# schematics.net
KiCad netlist of a schematic drawn in Altium Designer
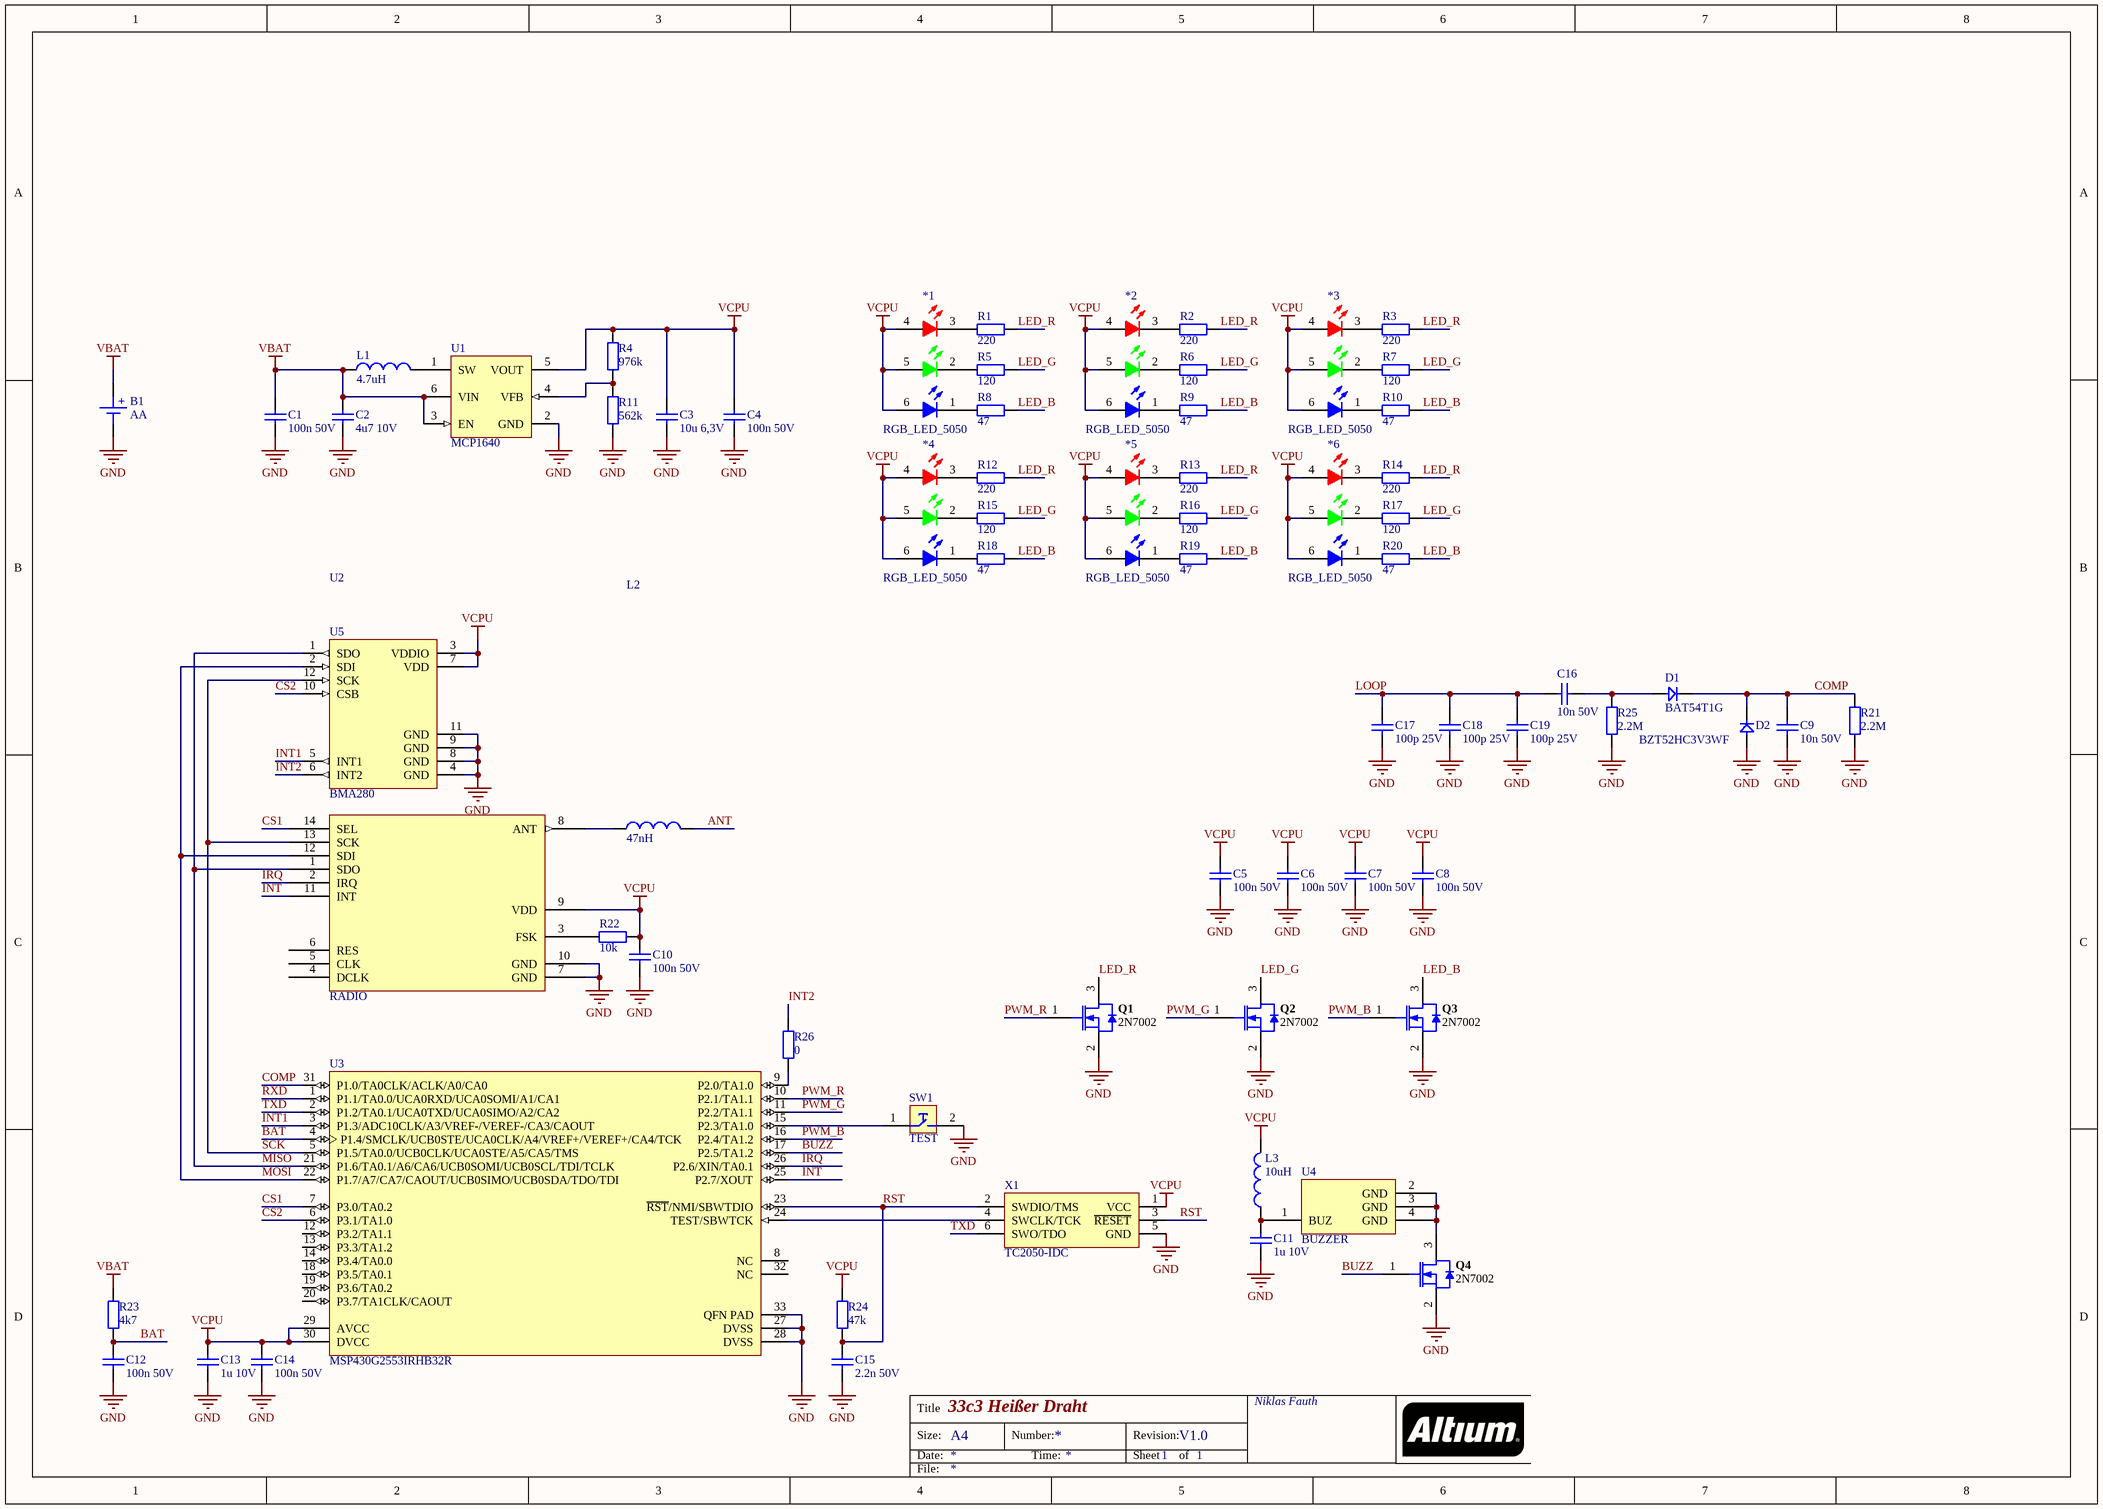
[diagram p0: schematics.SchDoc]

(export (version "E")
  (design (tool "Eeschema 10.0.6"))
  (components
    (comp (ref "*1")
      (value "RGB_LED_5050")
      (footprint "plcc6")
      (libsource (lib "advanced") (part "RGB_LED_5050"))
    )
    (comp (ref "*2")
      (value "RGB_LED_5050")
      (footprint "plcc6")
      (libsource (lib "advanced") (part "RGB_LED_5050"))
    )
    (comp (ref "*3")
      (value "RGB_LED_5050")
      (footprint "plcc6")
      (libsource (lib "advanced") (part "RGB_LED_5050"))
    )
    (comp (ref "*4")
      (value "RGB_LED_5050")
      (footprint "plcc6")
      (libsource (lib "advanced") (part "RGB_LED_5050"))
    )
    (comp (ref "*5")
      (value "RGB_LED_5050")
      (footprint "plcc6")
      (libsource (lib "advanced") (part "RGB_LED_5050"))
    )
    (comp (ref "*6")
      (value "RGB_LED_5050")
      (footprint "plcc6")
      (libsource (lib "advanced") (part "RGB_LED_5050"))
    )
    (comp (ref "B1")
      (value "AA")
      (footprint "AA-HOLDER")
      (description "Batt Holder AA")
      (libsource (lib "advanced") (part "AA-Batt-Holder"))
    )
    (comp (ref "C1")
      (value "100n 50V")
      (footprint "C-0603-M")
      (description "Capacitor 100n 50V")
      (libsource (lib "Passives") (part "C-0603-100n-50V"))
    )
    (comp (ref "C2")
      (value "4u7 10V")
      (footprint "C-0603-H")
      (description "Capacitor 4.7uF 10V")
      (libsource (lib "Passives") (part "C-0603-4u7-10V"))
    )
    (comp (ref "C3")
      (value "10u 6,3V")
      (footprint "C-0603-H")
      (description "Capacitor 10uF 6,3V")
      (libsource (lib "Passives") (part "C-0603-10u-6,3V"))
    )
    (comp (ref "C4")
      (value "100n 50V")
      (footprint "C-0603-M")
      (description "Capacitor 100n 50V")
      (libsource (lib "Passives") (part "C-0603-100n-50V"))
    )
    (comp (ref "C5")
      (value "100n 50V")
      (footprint "C-0603-M")
      (description "Capacitor 100n 50V")
      (libsource (lib "Passives") (part "C-0603-100n-50V"))
    )
    (comp (ref "C6")
      (value "100n 50V")
      (footprint "C-0603-M")
      (description "Capacitor 100n 50V")
      (libsource (lib "Passives") (part "C-0603-100n-50V"))
    )
    (comp (ref "C7")
      (value "100n 50V")
      (footprint "C-0603-M")
      (description "Capacitor 100n 50V")
      (libsource (lib "Passives") (part "C-0603-100n-50V"))
    )
    (comp (ref "C8")
      (value "100n 50V")
      (footprint "C-0603-M")
      (description "Capacitor 100n 50V")
      (libsource (lib "Passives") (part "C-0603-100n-50V"))
    )
    (comp (ref "C9")
      (value "10n 50V")
      (footprint "C-0603-H")
      (description "Capacitor 10nF 50V")
      (libsource (lib "Passives") (part "C-0603-10n-50V"))
    )
    (comp (ref "C10")
      (value "100n 50V")
      (footprint "C-0603-M")
      (description "Capacitor 100n 50V")
      (libsource (lib "Passives") (part "C-0603-100n-50V"))
    )
    (comp (ref "C11")
      (value "1u 10V")
      (footprint "C-0603-H")
      (description "Capacitor 1uF 10V")
      (libsource (lib "Passives") (part "C-0603-1u-10V"))
    )
    (comp (ref "C12")
      (value "100n 50V")
      (footprint "C-0603-M")
      (description "Capacitor 100n 50V")
      (libsource (lib "Passives") (part "C-0603-100n-50V"))
    )
    (comp (ref "C13")
      (value "1u 10V")
      (footprint "C-0603-H")
      (description "Capacitor 1uF 10V")
      (libsource (lib "Passives") (part "C-0603-1u-10V"))
    )
    (comp (ref "C14")
      (value "100n 50V")
      (footprint "C-0603-M")
      (description "Capacitor 100n 50V")
      (libsource (lib "Passives") (part "C-0603-100n-50V"))
    )
    (comp (ref "C15")
      (value "2.2n 50V")
      (footprint "C-0603-H")
      (description "Capacitor 2.2n 50V")
      (libsource (lib "Passives") (part "C-0603-2n2-50V"))
    )
    (comp (ref "C16")
      (value "10n 50V")
      (footprint "C-0603-H")
      (description "Capacitor 10nF 50V")
      (libsource (lib "Passives") (part "C-0603-10n-50V"))
    )
    (comp (ref "C17")
      (value "100p 25V")
      (footprint "C-0603-M")
      (description "Capacitor 100pF 25V")
      (libsource (lib "Passives") (part "C-0603-100p-25V"))
    )
    (comp (ref "C18")
      (value "100p 25V")
      (footprint "C-0603-M")
      (description "Capacitor 100pF 25V")
      (libsource (lib "Passives") (part "C-0603-100p-25V"))
    )
    (comp (ref "C19")
      (value "100p 25V")
      (footprint "C-0603-M")
      (description "Capacitor 100pF 25V")
      (libsource (lib "Passives") (part "C-0603-100p-25V"))
    )
    (comp (ref "D1") (value "BAT54T1G") (footprint "SOD123") (libsource (lib "advanced") (part "BAT54T1G")))
    (comp (ref "D2")
      (value "BZT52HC3V3WF")
      (footprint "SOD123")
      (description "BAT54T1G")
      (libsource (lib "advanced") (part "BAT54T1G"))
    )
    (comp (ref "L1")
      (value "4.7uH")
      (footprint "SRN4012")
      (description "SRN4012TA-4R7M")
      (libsource (lib "advanced") (part "L-SRN4012TA-4R7M"))
    )
    (comp (ref "L2") (value "47nH") (footprint "C-0603-M") (libsource (lib "advanced") (part "L-0603-47nH")))
    (comp (ref "L3")
      (value "10uH")
      (footprint "R-0805")
      (description "L 0805 10uH")
      (libsource (lib "advanced") (part "L-0805-10uH"))
    )
    (comp (ref "Q1")
      (value "2N7002")
      (footprint "INF-PG-SOT23_M")
      (fields (field (name "MANUFACTURER") "Infineon"))
      (libsource (lib "Altium Content Vault") (part "INF-NDMOS-GSD-3"))
    )
    (comp (ref "Q2")
      (value "2N7002")
      (footprint "INF-PG-SOT23_M")
      (fields (field (name "MANUFACTURER") "Infineon"))
      (libsource (lib "Altium Content Vault") (part "INF-NDMOS-GSD-3"))
    )
    (comp (ref "Q3")
      (value "2N7002")
      (footprint "INF-PG-SOT23_M")
      (fields (field (name "MANUFACTURER") "Infineon"))
      (libsource (lib "Altium Content Vault") (part "INF-NDMOS-GSD-3"))
    )
    (comp (ref "Q4")
      (value "2N7002")
      (footprint "INF-PG-SOT23_M")
      (fields (field (name "MANUFACTURER") "Infineon"))
      (libsource (lib "Altium Content Vault") (part "INF-NDMOS-GSD-3"))
    )
    (comp (ref "R1")
      (value "220")
      (footprint "R-0603-M")
      (description "Resistor 220")
      (libsource (lib "Passives") (part "R-0603-220"))
    )
    (comp (ref "R2")
      (value "220")
      (footprint "R-0603-M")
      (description "Resistor 220")
      (libsource (lib "Passives") (part "R-0603-220"))
    )
    (comp (ref "R3")
      (value "220")
      (footprint "R-0603-M")
      (description "Resistor 220")
      (libsource (lib "Passives") (part "R-0603-220"))
    )
    (comp (ref "R4")
      (value "976k")
      (footprint "R-0603-M")
      (description "Resistor 976k")
      (libsource (lib "Passives") (part "R-0603-976k"))
    )
    (comp (ref "R5")
      (value "120")
      (footprint "R-0603-M")
      (description "Resistor 120")
      (libsource (lib "Passives") (part "R-0603-120"))
    )
    (comp (ref "R6")
      (value "120")
      (footprint "R-0603-M")
      (description "Resistor 120")
      (libsource (lib "Passives") (part "R-0603-120"))
    )
    (comp (ref "R7")
      (value "120")
      (footprint "R-0603-M")
      (description "Resistor 120")
      (libsource (lib "Passives") (part "R-0603-120"))
    )
    (comp (ref "R8")
      (value "47")
      (footprint "R-0603-M")
      (description "Resistor 47")
      (libsource (lib "Passives") (part "R-0603-47"))
    )
    (comp (ref "R9")
      (value "47")
      (footprint "R-0603-M")
      (description "Resistor 47")
      (libsource (lib "Passives") (part "R-0603-47"))
    )
    (comp (ref "R10")
      (value "47")
      (footprint "R-0603-M")
      (description "Resistor 47")
      (libsource (lib "Passives") (part "R-0603-47"))
    )
    (comp (ref "R11")
      (value "562k")
      (footprint "R-0603-M")
      (description "Resistor 562k")
      (libsource (lib "Passives") (part "R-0603-562k"))
    )
    (comp (ref "R12")
      (value "220")
      (footprint "R-0603-M")
      (description "Resistor 220")
      (libsource (lib "Passives") (part "R-0603-220"))
    )
    (comp (ref "R13")
      (value "220")
      (footprint "R-0603-M")
      (description "Resistor 220")
      (libsource (lib "Passives") (part "R-0603-220"))
    )
    (comp (ref "R14")
      (value "220")
      (footprint "R-0603-M")
      (description "Resistor 220")
      (libsource (lib "Passives") (part "R-0603-220"))
    )
    (comp (ref "R15")
      (value "120")
      (footprint "R-0603-M")
      (description "Resistor 120")
      (libsource (lib "Passives") (part "R-0603-120"))
    )
    (comp (ref "R16")
      (value "120")
      (footprint "R-0603-M")
      (description "Resistor 120")
      (libsource (lib "Passives") (part "R-0603-120"))
    )
    (comp (ref "R17")
      (value "120")
      (footprint "R-0603-M")
      (description "Resistor 120")
      (libsource (lib "Passives") (part "R-0603-120"))
    )
    (comp (ref "R18")
      (value "47")
      (footprint "R-0603-M")
      (description "Resistor 47")
      (libsource (lib "Passives") (part "R-0603-47"))
    )
    (comp (ref "R19")
      (value "47")
      (footprint "R-0603-M")
      (description "Resistor 47")
      (libsource (lib "Passives") (part "R-0603-47"))
    )
    (comp (ref "R20")
      (value "47")
      (footprint "R-0603-M")
      (description "Resistor 47")
      (libsource (lib "Passives") (part "R-0603-47"))
    )
    (comp (ref "R21")
      (value "2.2M")
      (footprint "R-0603-H")
      (description "Resistor 2.2M")
      (libsource (lib "Passives") (part "R-0603-2M2"))
    )
    (comp (ref "R22")
      (value "10k")
      (footprint "R-0603-M")
      (description "Resistor 10k")
      (libsource (lib "Passives") (part "R-0603-10k"))
    )
    (comp (ref "R23")
      (value "4k7")
      (footprint "R-0603-H")
      (description "Resistor 4k7")
      (libsource (lib "Passives") (part "R-0603-4k7"))
    )
    (comp (ref "R24")
      (value "47k")
      (footprint "R-0603-H")
      (description "Resistor 4k7")
      (libsource (lib "Passives") (part "R-0603-47k"))
    )
    (comp (ref "R25")
      (value "2.2M")
      (footprint "R-0603-H")
      (description "Resistor 2.2M")
      (libsource (lib "Passives") (part "R-0603-2M2"))
    )
    (comp (ref "R26")
      (value "0")
      (footprint "R-0603-M")
      (description "Resistor 0")
      (libsource (lib "Passives") (part "R-0603-0"))
    )
    (comp (ref "SW1")
      (value "TEST")
      (footprint "switch-mini-ALPS")
      (description "SKQYAAE010")
      (libsource (lib "advanced") (part "Switch-mini-ALPS"))
    )
    (comp (ref "U1")
      (value "MCP1640")
      (footprint "SOT23-6")
      (description "aaa to 3.3V")
      (libsource (lib "advanced") (part "MCP1640"))
    )
    (comp (ref "U2")
      (value "RADIO")
      (footprint "RFM12")
      (description "Sub 1GHz Radio Module")
      (libsource (lib "advanced") (part "RFM12"))
    )
    (comp (ref "U3")
      (value "MSP430G2553IRHB32R")
      (footprint "RHB0032E_V")
      (fields (field (name "MANUFACTURER") "Texas Instruments"))
      (libsource (lib "Altium Content Vault") (part "TI-MSP430G2X53-RHB32"))
    )
    (comp (ref "U4") (value "BUZZER") (footprint "PIEZO") (libsource (lib "advanced") (part "PIEZO-1411A03")))
    (comp (ref "U5")
      (value "BMA280")
      (footprint "LGA12C50P4X4_203X203X80")
      (libsource (lib "advanced") (part "BMA280"))
    )
    (comp (ref "X1")
      (value "TC2050-IDC")
      (footprint "TC2030-IDC-NL")
      (description "TC2050-IDC SWD")
      (libsource (lib "advanced") (part "TAG-Connect-SWD"))
    )
  )
  (nets
    (net (code "1") (name "/ANT") (class "Default")
      (node (ref "L2") (pin "2") (pinfunction "2_2") (pintype "passive"))
    )
    (net (code "2") (name "/BAT") (class "Default")
      (node (ref "C12") (pin "2") (pinfunction "2_2") (pintype "passive"))
      (node (ref "R23") (pin "1") (pinfunction "1_1") (pintype "passive"))
      (node (ref "U3") (pin "4") (pinfunction "P1.4/SMCLK/UCB0STE/UCA0CLK/A4/VREF+/VEREF+/CA4/TCK_4") (pintype "bidirectional"))
    )
    (net (code "3") (name "/BUZZ") (class "Default")
      (node (ref "Q4") (pin "1") (pinfunction "GATE_1") (pintype "passive"))
      (node (ref "U3") (pin "17") (pinfunction "P2.5/TA1.2_17") (pintype "bidirectional"))
    )
    (net (code "4") (name "/COMP") (class "Default")
      (node (ref "C9") (pin "2") (pinfunction "2_2") (pintype "passive"))
      (node (ref "D1") (pin "2") (pinfunction "kt_2") (pintype "passive"))
      (node (ref "D2") (pin "2") (pinfunction "kt_2") (pintype "passive"))
      (node (ref "R21") (pin "2") (pinfunction "2_2") (pintype "passive"))
      (node (ref "U3") (pin "31") (pinfunction "P1.0/TA0CLK/ACLK/A0/CA0_31") (pintype "bidirectional"))
    )
    (net (code "5") (name "/CS1") (class "Default")
      (node (ref "U2") (pin "14") (pinfunction "SEL_14") (pintype "passive"))
      (node (ref "U3") (pin "7") (pinfunction "P3.0/TA0.2_7") (pintype "bidirectional"))
    )
    (net (code "6") (name "/CS2") (class "Default")
      (node (ref "U3") (pin "6") (pinfunction "P3.1/TA1.0_6") (pintype "bidirectional"))
      (node (ref "U5") (pin "10") (pinfunction "CSB_10") (pintype "input"))
    )
    (net (code "7") (name "/INT") (class "Default")
      (node (ref "U2") (pin "11") (pinfunction "INT_11") (pintype "passive"))
      (node (ref "U3") (pin "25") (pinfunction "P2.7/XOUT_25") (pintype "bidirectional"))
    )
    (net (code "8") (name "/INT1") (class "Default")
      (node (ref "U3") (pin "3") (pinfunction "P1.3/ADC10CLK/A3/VREF-/VEREF-/CA3/CAOUT_3") (pintype "bidirectional"))
      (node (ref "U5") (pin "5") (pinfunction "INT1_5") (pintype "output"))
    )
    (net (code "9") (name "/INT2") (class "Default")
      (node (ref "R26") (pin "2") (pinfunction "2_2") (pintype "passive"))
      (node (ref "U5") (pin "6") (pinfunction "INT2_6") (pintype "output"))
    )
    (net (code "10") (name "/IRQ") (class "Default")
      (node (ref "U2") (pin "2") (pinfunction "IRQ_2") (pintype "passive"))
      (node (ref "U3") (pin "26") (pinfunction "P2.6/XIN/TA0.1_26") (pintype "bidirectional"))
    )
    (net (code "11") (name "/LED_B") (class "Default")
      (node (ref "Q3") (pin "3") (pinfunction "DRAIN_3") (pintype "passive"))
      (node (ref "R10") (pin "2") (pinfunction "2_2") (pintype "passive"))
      (node (ref "R18") (pin "2") (pinfunction "2_2") (pintype "passive"))
      (node (ref "R19") (pin "2") (pinfunction "2_2") (pintype "passive"))
      (node (ref "R20") (pin "2") (pinfunction "2_2") (pintype "passive"))
      (node (ref "R8") (pin "2") (pinfunction "2_2") (pintype "passive"))
      (node (ref "R9") (pin "2") (pinfunction "2_2") (pintype "passive"))
    )
    (net (code "12") (name "/LED_G") (class "Default")
      (node (ref "Q2") (pin "3") (pinfunction "DRAIN_3") (pintype "passive"))
      (node (ref "R15") (pin "2") (pinfunction "2_2") (pintype "passive"))
      (node (ref "R16") (pin "2") (pinfunction "2_2") (pintype "passive"))
      (node (ref "R17") (pin "2") (pinfunction "2_2") (pintype "passive"))
      (node (ref "R5") (pin "2") (pinfunction "2_2") (pintype "passive"))
      (node (ref "R6") (pin "2") (pinfunction "2_2") (pintype "passive"))
      (node (ref "R7") (pin "2") (pinfunction "2_2") (pintype "passive"))
    )
    (net (code "13") (name "/LED_R") (class "Default")
      (node (ref "Q1") (pin "3") (pinfunction "DRAIN_3") (pintype "passive"))
      (node (ref "R1") (pin "2") (pinfunction "2_2") (pintype "passive"))
      (node (ref "R12") (pin "2") (pinfunction "2_2") (pintype "passive"))
      (node (ref "R13") (pin "2") (pinfunction "2_2") (pintype "passive"))
      (node (ref "R14") (pin "2") (pinfunction "2_2") (pintype "passive"))
      (node (ref "R2") (pin "2") (pinfunction "2_2") (pintype "passive"))
      (node (ref "R3") (pin "2") (pinfunction "2_2") (pintype "passive"))
    )
    (net (code "14") (name "/LOOP") (class "Default")
      (node (ref "C16") (pin "1") (pinfunction "1_1") (pintype "passive"))
      (node (ref "C17") (pin "2") (pinfunction "2_2") (pintype "passive"))
      (node (ref "C18") (pin "2") (pinfunction "2_2") (pintype "passive"))
      (node (ref "C19") (pin "2") (pinfunction "2_2") (pintype "passive"))
    )
    (net (code "15") (name "/MISO") (class "Default")
      (node (ref "U2") (pin "1") (pinfunction "SDO_1") (pintype "passive"))
      (node (ref "U3") (pin "21") (pinfunction "P1.6/TA0.1/A6/CA6/UCB0SOMI/UCB0SCL/TDI/TCLK_21") (pintype "bidirectional"))
      (node (ref "U5") (pin "1") (pinfunction "SDO_1") (pintype "output"))
    )
    (net (code "16") (name "/MOSI") (class "Default")
      (node (ref "U2") (pin "12") (pinfunction "SDI_12") (pintype "passive"))
      (node (ref "U3") (pin "22") (pinfunction "P1.7/A7/CA7/CAOUT/UCB0SIMO/UCB0SDA/TDO/TDI_22") (pintype "bidirectional"))
      (node (ref "U5") (pin "2") (pinfunction "SDI_2") (pintype "input"))
    )
    (net (code "17") (name "/PWM_B") (class "Default")
      (node (ref "Q3") (pin "1") (pinfunction "GATE_1") (pintype "passive"))
      (node (ref "U3") (pin "16") (pinfunction "P2.4/TA1.2_16") (pintype "bidirectional"))
    )
    (net (code "18") (name "/PWM_G") (class "Default")
      (node (ref "Q2") (pin "1") (pinfunction "GATE_1") (pintype "passive"))
      (node (ref "U3") (pin "11") (pinfunction "P2.2/TA1.1_11") (pintype "bidirectional"))
    )
    (net (code "19") (name "/PWM_R") (class "Default")
      (node (ref "Q1") (pin "1") (pinfunction "GATE_1") (pintype "passive"))
      (node (ref "U3") (pin "10") (pinfunction "P2.1/TA1.1_10") (pintype "bidirectional"))
    )
    (net (code "20") (name "/RST") (class "Default")
      (node (ref "C15") (pin "2") (pinfunction "2_2") (pintype "passive"))
      (node (ref "R24") (pin "1") (pinfunction "1_1") (pintype "passive"))
      (node (ref "U3") (pin "23") (pinfunction "~{RST}/NMI/SBWTDIO_23") (pintype "bidirectional"))
      (node (ref "X1") (pin "2") (pinfunction "SWDIO/TMS_2") (pintype "passive"))
      (node (ref "X1") (pin "3") (pinfunction "~{RESET}_3") (pintype "passive"))
    )
    (net (code "21") (name "/RXD") (class "Default")
      (node (ref "U3") (pin "1") (pinfunction "P1.1/TA0.0/UCA0RXD/UCA0SOMI/A1/CA1_1") (pintype "bidirectional"))
    )
    (net (code "22") (name "/SCK") (class "Default")
      (node (ref "U2") (pin "13") (pinfunction "SCK_13") (pintype "passive"))
      (node (ref "U3") (pin "5") (pinfunction "P1.5/TA0.0/UCB0CLK/UCA0STE/A5/CA5/TMS_5") (pintype "bidirectional"))
      (node (ref "U5") (pin "12") (pinfunction "SCK_12") (pintype "input"))
    )
    (net (code "23") (name "/TXD") (class "Default")
      (node (ref "U3") (pin "2") (pinfunction "P1.2/TA0.1/UCA0TXD/UCA0SIMO/A2/CA2_2") (pintype "bidirectional"))
      (node (ref "X1") (pin "6") (pinfunction "SWO/TDO_6") (pintype "passive"))
    )
    (net (code "24") (name "GND") (class "Default")
      (node (ref "B1") (pin "1") (pintype "passive"))
      (node (ref "C1") (pin "1") (pinfunction "1_1") (pintype "passive"))
      (node (ref "C10") (pin "1") (pinfunction "1_1") (pintype "passive"))
      (node (ref "C11") (pin "1") (pinfunction "1_1") (pintype "passive"))
      (node (ref "C12") (pin "1") (pinfunction "1_1") (pintype "passive"))
      (node (ref "C13") (pin "1") (pinfunction "1_1") (pintype "passive"))
      (node (ref "C14") (pin "1") (pinfunction "1_1") (pintype "passive"))
      (node (ref "C15") (pin "1") (pinfunction "1_1") (pintype "passive"))
      (node (ref "C17") (pin "1") (pinfunction "1_1") (pintype "passive"))
      (node (ref "C18") (pin "1") (pinfunction "1_1") (pintype "passive"))
      (node (ref "C19") (pin "1") (pinfunction "1_1") (pintype "passive"))
      (node (ref "C2") (pin "1") (pinfunction "1_1") (pintype "passive"))
      (node (ref "C3") (pin "1") (pinfunction "1_1") (pintype "passive"))
      (node (ref "C4") (pin "1") (pinfunction "1_1") (pintype "passive"))
      (node (ref "C5") (pin "1") (pinfunction "1_1") (pintype "passive"))
      (node (ref "C6") (pin "1") (pinfunction "1_1") (pintype "passive"))
      (node (ref "C7") (pin "1") (pinfunction "1_1") (pintype "passive"))
      (node (ref "C8") (pin "1") (pinfunction "1_1") (pintype "passive"))
      (node (ref "C9") (pin "1") (pinfunction "1_1") (pintype "passive"))
      (node (ref "D2") (pin "1") (pinfunction "an_1") (pintype "passive"))
      (node (ref "Q1") (pin "2") (pinfunction "SOURCE_2") (pintype "passive"))
      (node (ref "Q2") (pin "2") (pinfunction "SOURCE_2") (pintype "passive"))
      (node (ref "Q3") (pin "2") (pinfunction "SOURCE_2") (pintype "passive"))
      (node (ref "Q4") (pin "2") (pinfunction "SOURCE_2") (pintype "passive"))
      (node (ref "R11") (pin "1") (pinfunction "1_1") (pintype "passive"))
      (node (ref "R21") (pin "1") (pinfunction "1_1") (pintype "passive"))
      (node (ref "R25") (pin "1") (pinfunction "1_1") (pintype "passive"))
      (node (ref "SW1") (pin "2") (pintype "passive"))
      (node (ref "U1") (pin "2") (pinfunction "GND_2") (pintype "power_in"))
      (node (ref "U2") (pin "10") (pinfunction "GND_10") (pintype "passive"))
      (node (ref "U2") (pin "7") (pinfunction "GND_7") (pintype "passive"))
      (node (ref "U3") (pin "27") (pinfunction "DVSS_27") (pintype "power_in"))
      (node (ref "U3") (pin "28") (pinfunction "DVSS_28") (pintype "power_in"))
      (node (ref "U3") (pin "33") (pinfunction "QFN_PAD_33") (pintype "power_in"))
      (node (ref "U5") (pin "11") (pinfunction "GND_11") (pintype "power_in"))
      (node (ref "U5") (pin "4") (pinfunction "GND_4") (pintype "power_in"))
      (node (ref "U5") (pin "8") (pinfunction "GND_8") (pintype "power_in"))
      (node (ref "U5") (pin "9") (pinfunction "GND_9") (pintype "power_in"))
      (node (ref "X1") (pin "5") (pinfunction "GND_5") (pintype "passive"))
    )
    (net (code "25") (name "Net-(*1-K-Pad1)") (class "Default")
      (node (ref "*1") (pin "1") (pinfunction "K_1") (pintype "passive"))
      (node (ref "R8") (pin "1") (pinfunction "1_1") (pintype "passive"))
    )
    (net (code "26") (name "Net-(*1-K-Pad2)") (class "Default")
      (node (ref "*1") (pin "2") (pinfunction "K_2") (pintype "passive"))
      (node (ref "R5") (pin "1") (pinfunction "1_1") (pintype "passive"))
    )
    (net (code "27") (name "Net-(*1-K-Pad3)") (class "Default")
      (node (ref "*1") (pin "3") (pinfunction "K_3") (pintype "passive"))
      (node (ref "R1") (pin "1") (pinfunction "1_1") (pintype "passive"))
    )
    (net (code "28") (name "Net-(*2-K-Pad1)") (class "Default")
      (node (ref "*2") (pin "1") (pinfunction "K_1") (pintype "passive"))
      (node (ref "R9") (pin "1") (pinfunction "1_1") (pintype "passive"))
    )
    (net (code "29") (name "Net-(*2-K-Pad2)") (class "Default")
      (node (ref "*2") (pin "2") (pinfunction "K_2") (pintype "passive"))
      (node (ref "R6") (pin "1") (pinfunction "1_1") (pintype "passive"))
    )
    (net (code "30") (name "Net-(*2-K-Pad3)") (class "Default")
      (node (ref "*2") (pin "3") (pinfunction "K_3") (pintype "passive"))
      (node (ref "R2") (pin "1") (pinfunction "1_1") (pintype "passive"))
    )
    (net (code "31") (name "Net-(*3-K-Pad1)") (class "Default")
      (node (ref "*3") (pin "1") (pinfunction "K_1") (pintype "passive"))
      (node (ref "R10") (pin "1") (pinfunction "1_1") (pintype "passive"))
    )
    (net (code "32") (name "Net-(*3-K-Pad2)") (class "Default")
      (node (ref "*3") (pin "2") (pinfunction "K_2") (pintype "passive"))
      (node (ref "R7") (pin "1") (pinfunction "1_1") (pintype "passive"))
    )
    (net (code "33") (name "Net-(*3-K-Pad3)") (class "Default")
      (node (ref "*3") (pin "3") (pinfunction "K_3") (pintype "passive"))
      (node (ref "R3") (pin "1") (pinfunction "1_1") (pintype "passive"))
    )
    (net (code "34") (name "Net-(*4-K-Pad1)") (class "Default")
      (node (ref "*4") (pin "1") (pinfunction "K_1") (pintype "passive"))
      (node (ref "R18") (pin "1") (pinfunction "1_1") (pintype "passive"))
    )
    (net (code "35") (name "Net-(*4-K-Pad2)") (class "Default")
      (node (ref "*4") (pin "2") (pinfunction "K_2") (pintype "passive"))
      (node (ref "R15") (pin "1") (pinfunction "1_1") (pintype "passive"))
    )
    (net (code "36") (name "Net-(*4-K-Pad3)") (class "Default")
      (node (ref "*4") (pin "3") (pinfunction "K_3") (pintype "passive"))
      (node (ref "R12") (pin "1") (pinfunction "1_1") (pintype "passive"))
    )
    (net (code "37") (name "Net-(*5-K-Pad1)") (class "Default")
      (node (ref "*5") (pin "1") (pinfunction "K_1") (pintype "passive"))
      (node (ref "R19") (pin "1") (pinfunction "1_1") (pintype "passive"))
    )
    (net (code "38") (name "Net-(*5-K-Pad2)") (class "Default")
      (node (ref "*5") (pin "2") (pinfunction "K_2") (pintype "passive"))
      (node (ref "R16") (pin "1") (pinfunction "1_1") (pintype "passive"))
    )
    (net (code "39") (name "Net-(*5-K-Pad3)") (class "Default")
      (node (ref "*5") (pin "3") (pinfunction "K_3") (pintype "passive"))
      (node (ref "R13") (pin "1") (pinfunction "1_1") (pintype "passive"))
    )
    (net (code "40") (name "Net-(*6-K-Pad1)") (class "Default")
      (node (ref "*6") (pin "1") (pinfunction "K_1") (pintype "passive"))
      (node (ref "R20") (pin "1") (pinfunction "1_1") (pintype "passive"))
    )
    (net (code "41") (name "Net-(*6-K-Pad2)") (class "Default")
      (node (ref "*6") (pin "2") (pinfunction "K_2") (pintype "passive"))
      (node (ref "R17") (pin "1") (pinfunction "1_1") (pintype "passive"))
    )
    (net (code "42") (name "Net-(*6-K-Pad3)") (class "Default")
      (node (ref "*6") (pin "3") (pinfunction "K_3") (pintype "passive"))
      (node (ref "R14") (pin "1") (pinfunction "1_1") (pintype "passive"))
    )
    (net (code "43") (name "Net-(D1-an)") (class "Default")
      (node (ref "C16") (pin "2") (pinfunction "2_2") (pintype "passive"))
      (node (ref "D1") (pin "1") (pinfunction "an_1") (pintype "passive"))
      (node (ref "R25") (pin "2") (pinfunction "2_2") (pintype "passive"))
    )
    (net (code "44") (name "Net-(Q4-DRAIN)") (class "Default")
      (node (ref "Q4") (pin "3") (pinfunction "DRAIN_3") (pintype "passive"))
      (node (ref "U4") (pin "2") (pinfunction "GND_2") (pintype "passive"))
      (node (ref "U4") (pin "3") (pinfunction "GND_3") (pintype "passive"))
      (node (ref "U4") (pin "4") (pinfunction "GND_4") (pintype "passive"))
    )
    (net (code "45") (name "Net-(U1-SW)") (class "Default")
      (node (ref "L1") (pin "2") (pinfunction "2_2") (pintype "passive"))
      (node (ref "U1") (pin "1") (pinfunction "SW_1") (pintype "passive"))
    )
    (net (code "46") (name "Net-(U1-VFB)") (class "Default")
      (node (ref "R11") (pin "2") (pinfunction "2_2") (pintype "passive"))
      (node (ref "R4") (pin "1") (pinfunction "1_1") (pintype "passive"))
      (node (ref "U1") (pin "4") (pinfunction "VFB_4") (pintype "input"))
    )
    (net (code "47") (name "Net-(U2-ANT)") (class "Default")
      (node (ref "L2") (pin "1") (pinfunction "1_1") (pintype "passive"))
      (node (ref "U2") (pin "8") (pinfunction "ANT_8") (pintype "output"))
    )
    (net (code "48") (name "Net-(U2-FSK)") (class "Default")
      (node (ref "R22") (pin "1") (pinfunction "1_1") (pintype "passive"))
      (node (ref "U2") (pin "3") (pinfunction "FSK_3") (pintype "passive"))
    )
    (net (code "49") (name "Net-(U3-P2.0{slash}TA1.0)") (class "Default")
      (node (ref "R26") (pin "1") (pinfunction "1_1") (pintype "passive"))
      (node (ref "U3") (pin "9") (pinfunction "P2.0/TA1.0_9") (pintype "bidirectional"))
    )
    (net (code "50") (name "Net-(U3-P2.3{slash}TA1.0)") (class "Default")
      (node (ref "SW1") (pin "1") (pintype "passive"))
      (node (ref "U3") (pin "15") (pinfunction "P2.3/TA1.0_15") (pintype "bidirectional"))
    )
    (net (code "51") (name "Net-(U3-TEST{slash}SBWTCK)") (class "Default")
      (node (ref "U3") (pin "24") (pinfunction "TEST/SBWTCK_24") (pintype "input"))
      (node (ref "X1") (pin "4") (pinfunction "SWCLK/TCK_4") (pintype "passive"))
    )
    (net (code "52") (name "Net-(U4-BUZ)") (class "Default")
      (node (ref "C11") (pin "2") (pinfunction "2_2") (pintype "passive"))
      (node (ref "L3") (pin "1") (pinfunction "1_1") (pintype "passive"))
      (node (ref "U4") (pin "1") (pinfunction "BUZ_1") (pintype "passive"))
    )
    (net (code "53") (name "VBAT") (class "Default")
      (node (ref "B1") (pin "2") (pintype "passive"))
      (node (ref "C1") (pin "2") (pinfunction "2_2") (pintype "passive"))
      (node (ref "C2") (pin "2") (pinfunction "2_2") (pintype "passive"))
      (node (ref "L1") (pin "1") (pinfunction "1_1") (pintype "passive"))
      (node (ref "R23") (pin "2") (pinfunction "2_2") (pintype "passive"))
      (node (ref "U1") (pin "3") (pinfunction "EN_3") (pintype "input"))
      (node (ref "U1") (pin "6") (pinfunction "VIN_6") (pintype "power_in"))
    )
    (net (code "54") (name "VCPU") (class "Default")
      (node (ref "*1") (pin "4") (pinfunction "A_4") (pintype "passive"))
      (node (ref "*1") (pin "5") (pinfunction "A_5") (pintype "passive"))
      (node (ref "*1") (pin "6") (pinfunction "A_6") (pintype "passive"))
      (node (ref "*2") (pin "4") (pinfunction "A_4") (pintype "passive"))
      (node (ref "*2") (pin "5") (pinfunction "A_5") (pintype "passive"))
      (node (ref "*2") (pin "6") (pinfunction "A_6") (pintype "passive"))
      (node (ref "*3") (pin "4") (pinfunction "A_4") (pintype "passive"))
      (node (ref "*3") (pin "5") (pinfunction "A_5") (pintype "passive"))
      (node (ref "*3") (pin "6") (pinfunction "A_6") (pintype "passive"))
      (node (ref "*4") (pin "4") (pinfunction "A_4") (pintype "passive"))
      (node (ref "*4") (pin "5") (pinfunction "A_5") (pintype "passive"))
      (node (ref "*4") (pin "6") (pinfunction "A_6") (pintype "passive"))
      (node (ref "*5") (pin "4") (pinfunction "A_4") (pintype "passive"))
      (node (ref "*5") (pin "5") (pinfunction "A_5") (pintype "passive"))
      (node (ref "*5") (pin "6") (pinfunction "A_6") (pintype "passive"))
      (node (ref "*6") (pin "4") (pinfunction "A_4") (pintype "passive"))
      (node (ref "*6") (pin "5") (pinfunction "A_5") (pintype "passive"))
      (node (ref "*6") (pin "6") (pinfunction "A_6") (pintype "passive"))
      (node (ref "C10") (pin "2") (pinfunction "2_2") (pintype "passive"))
      (node (ref "C13") (pin "2") (pinfunction "2_2") (pintype "passive"))
      (node (ref "C14") (pin "2") (pinfunction "2_2") (pintype "passive"))
      (node (ref "C3") (pin "2") (pinfunction "2_2") (pintype "passive"))
      (node (ref "C4") (pin "2") (pinfunction "2_2") (pintype "passive"))
      (node (ref "C5") (pin "2") (pinfunction "2_2") (pintype "passive"))
      (node (ref "C6") (pin "2") (pinfunction "2_2") (pintype "passive"))
      (node (ref "C7") (pin "2") (pinfunction "2_2") (pintype "passive"))
      (node (ref "C8") (pin "2") (pinfunction "2_2") (pintype "passive"))
      (node (ref "L3") (pin "2") (pinfunction "2_2") (pintype "passive"))
      (node (ref "R22") (pin "2") (pinfunction "2_2") (pintype "passive"))
      (node (ref "R24") (pin "2") (pinfunction "2_2") (pintype "passive"))
      (node (ref "R4") (pin "2") (pinfunction "2_2") (pintype "passive"))
      (node (ref "U1") (pin "5") (pinfunction "VOUT_5") (pintype "power_in"))
      (node (ref "U2") (pin "9") (pinfunction "VDD_9") (pintype "passive"))
      (node (ref "U3") (pin "29") (pinfunction "AVCC_29") (pintype "power_in"))
      (node (ref "U3") (pin "30") (pinfunction "DVCC_30") (pintype "power_in"))
      (node (ref "U5") (pin "3") (pinfunction "VDDIO_3") (pintype "power_in"))
      (node (ref "U5") (pin "7") (pinfunction "VDD_7") (pintype "power_in"))
      (node (ref "X1") (pin "1") (pinfunction "VCC_1") (pintype "passive"))
    )
    (net (code "55") (name "unconnected-(U2-CLK-Pad5)") (class "Default")
      (node (ref "U2") (pin "5") (pinfunction "CLK_5") (pintype "passive"))
    )
    (net (code "56") (name "unconnected-(U2-DCLK-Pad4)") (class "Default")
      (node (ref "U2") (pin "4") (pinfunction "DCLK_4") (pintype "passive"))
    )
    (net (code "57") (name "unconnected-(U2-RES-Pad6)") (class "Default")
      (node (ref "U2") (pin "6") (pinfunction "RES_6") (pintype "passive"))
    )
    (net (code "58") (name "unconnected-(U3-NC-Pad8)") (class "Default")
      (node (ref "U3") (pin "8") (pinfunction "NC_8") (pintype "passive"))
    )
    (net (code "59") (name "unconnected-(U3-NC-Pad32)") (class "Default")
      (node (ref "U3") (pin "32") (pinfunction "NC_32") (pintype "passive"))
    )
    (net (code "60") (name "unconnected-(U3-P3.2{slash}TA1.1-Pad12)") (class "Default")
      (node (ref "U3") (pin "12") (pinfunction "P3.2/TA1.1_12") (pintype "bidirectional"))
    )
    (net (code "61") (name "unconnected-(U3-P3.3{slash}TA1.2-Pad13)") (class "Default")
      (node (ref "U3") (pin "13") (pinfunction "P3.3/TA1.2_13") (pintype "bidirectional"))
    )
    (net (code "62") (name "unconnected-(U3-P3.4{slash}TA0.0-Pad14)") (class "Default")
      (node (ref "U3") (pin "14") (pinfunction "P3.4/TA0.0_14") (pintype "bidirectional"))
    )
    (net (code "63") (name "unconnected-(U3-P3.5{slash}TA0.1-Pad18)") (class "Default")
      (node (ref "U3") (pin "18") (pinfunction "P3.5/TA0.1_18") (pintype "bidirectional"))
    )
    (net (code "64") (name "unconnected-(U3-P3.6{slash}TA0.2-Pad19)") (class "Default")
      (node (ref "U3") (pin "19") (pinfunction "P3.6/TA0.2_19") (pintype "bidirectional"))
    )
    (net (code "65") (name "unconnected-(U3-P3.7{slash}TA1CLK{slash}CAOUT-Pad20)") (class "Default")
      (node (ref "U3") (pin "20") (pinfunction "P3.7/TA1CLK/CAOUT_20") (pintype "bidirectional"))
    )
  )
)
